# 06_-_TEMP_HUM_CUR_SENSORS.net
KiCad netlist of a schematic drawn in Altium Designer
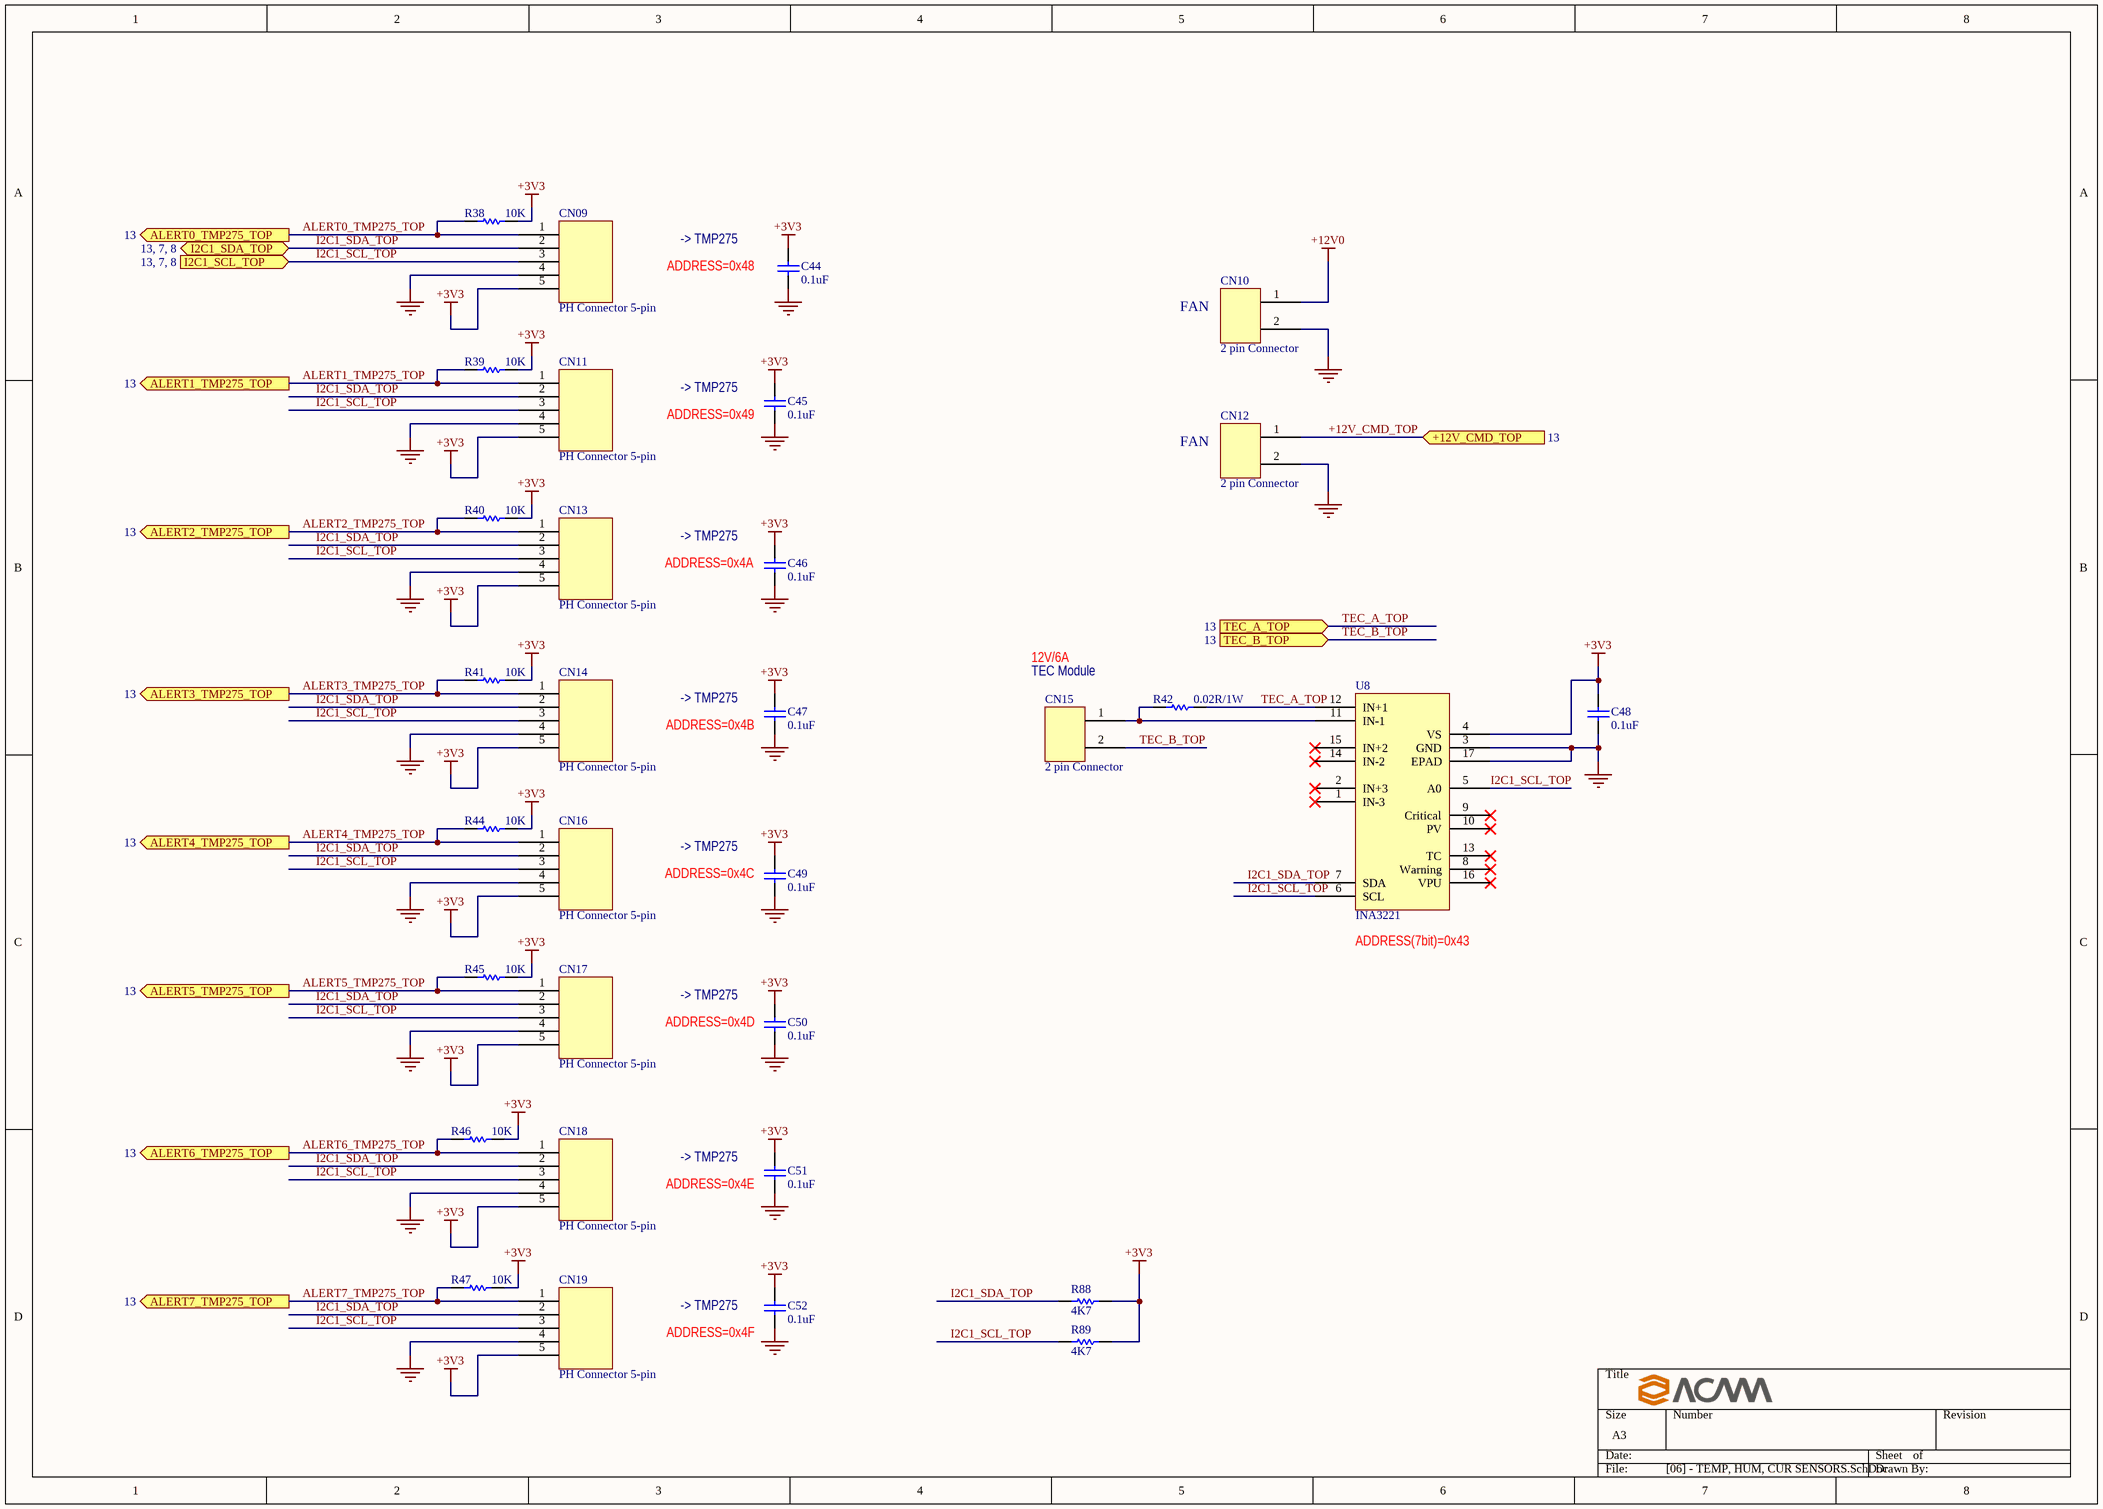
[diagram p0: [06] - TEMP, HUM, CUR SENSORS.SchDoc]

(export (version "E")
  (design (tool "Eeschema 10.0.6"))
  (components
    (comp (ref "C44")
      (value "0.1uF")
      (footprint "0805_C_AUTO")
      (description "Non-Pol SMD Capacitor")
      (libsource (lib "Farzan Custom Library") (part "Cap SMD"))
    )
    (comp (ref "C45")
      (value "0.1uF")
      (footprint "0805_C_AUTO")
      (description "Non-Pol SMD Capacitor")
      (libsource (lib "Farzan Custom Library") (part "Cap SMD"))
    )
    (comp (ref "C46")
      (value "0.1uF")
      (footprint "0805_C_AUTO")
      (description "Non-Pol SMD Capacitor")
      (libsource (lib "Farzan Custom Library") (part "Cap SMD"))
    )
    (comp (ref "C47")
      (value "0.1uF")
      (footprint "0805_C_AUTO")
      (description "Non-Pol SMD Capacitor")
      (libsource (lib "Farzan Custom Library") (part "Cap SMD"))
    )
    (comp (ref "C48")
      (value "0.1uF")
      (footprint "0805_C_AUTO")
      (description "Non-Pol SMD Capacitor")
      (libsource (lib "Farzan Custom Library") (part "Cap SMD"))
    )
    (comp (ref "C49")
      (value "0.1uF")
      (footprint "0805_C_AUTO")
      (description "Non-Pol SMD Capacitor")
      (libsource (lib "Farzan Custom Library") (part "Cap SMD"))
    )
    (comp (ref "C50")
      (value "0.1uF")
      (footprint "0805_C_AUTO")
      (description "Non-Pol SMD Capacitor")
      (libsource (lib "Farzan Custom Library") (part "Cap SMD"))
    )
    (comp (ref "C51")
      (value "0.1uF")
      (footprint "0805_C_AUTO")
      (description "Non-Pol SMD Capacitor")
      (libsource (lib "Farzan Custom Library") (part "Cap SMD"))
    )
    (comp (ref "C52")
      (value "0.1uF")
      (footprint "0805_C_AUTO")
      (description "Non-Pol SMD Capacitor")
      (libsource (lib "Farzan Custom Library") (part "Cap SMD"))
    )
    (comp (ref "CN09")
      (value "PH Connector 5-pin")
      (footprint "PH_5PIN")
      (description "PH Connector , 5 pin, 2mm pitch, straight")
      (libsource (lib "Farzan Custom Library") (part "PH Connector 5-pin"))
    )
    (comp (ref "CN10")
      (value "2 pin Connector")
      (footprint "KF142R_CONN_2PIN")
      (description "KAIFENG Screwless Connector 2 pin")
      (fields (field (name "MANUFACTURER PART NUM") "KF142R"))
      (libsource (lib "Farzan Custom Library") (part "Connector Screwless 2 pin"))
    )
    (comp (ref "CN11")
      (value "PH Connector 5-pin")
      (footprint "PH_5PIN")
      (description "PH Connector , 5 pin, 2mm pitch, straight")
      (libsource (lib "Farzan Custom Library") (part "PH Connector 5-pin"))
    )
    (comp (ref "CN12")
      (value "2 pin Connector")
      (footprint "KF142R_CONN_2PIN")
      (description "KAIFENG Screwless Connector 2 pin")
      (fields (field (name "MANUFACTURER PART NUM") "KF142R"))
      (libsource (lib "Farzan Custom Library") (part "Connector Screwless 2 pin"))
    )
    (comp (ref "CN13")
      (value "PH Connector 5-pin")
      (footprint "PH_5PIN")
      (description "PH Connector , 5 pin, 2mm pitch, straight")
      (libsource (lib "Farzan Custom Library") (part "PH Connector 5-pin"))
    )
    (comp (ref "CN14")
      (value "PH Connector 5-pin")
      (footprint "PH_5PIN")
      (description "PH Connector , 5 pin, 2mm pitch, straight")
      (libsource (lib "Farzan Custom Library") (part "PH Connector 5-pin"))
    )
    (comp (ref "CN15")
      (value "2 pin Connector")
      (footprint "KF142R_CONN_2PIN")
      (description "KAIFENG Screwless Connector 2 pin")
      (fields (field (name "MANUFACTURER PART NUM") "KF142R"))
      (libsource (lib "Farzan Custom Library") (part "Connector Screwless 2 pin"))
    )
    (comp (ref "CN16")
      (value "PH Connector 5-pin")
      (footprint "PH_5PIN")
      (description "PH Connector , 5 pin, 2mm pitch, straight")
      (libsource (lib "Farzan Custom Library") (part "PH Connector 5-pin"))
    )
    (comp (ref "CN17")
      (value "PH Connector 5-pin")
      (footprint "PH_5PIN")
      (description "PH Connector , 5 pin, 2mm pitch, straight")
      (libsource (lib "Farzan Custom Library") (part "PH Connector 5-pin"))
    )
    (comp (ref "CN18")
      (value "PH Connector 5-pin")
      (footprint "PH_5PIN")
      (description "PH Connector , 5 pin, 2mm pitch, straight")
      (libsource (lib "Farzan Custom Library") (part "PH Connector 5-pin"))
    )
    (comp (ref "CN19")
      (value "PH Connector 5-pin")
      (footprint "PH_5PIN")
      (description "PH Connector , 5 pin, 2mm pitch, straight")
      (libsource (lib "Farzan Custom Library") (part "PH Connector 5-pin"))
    )
    (comp (ref "R38")
      (value "10K")
      (footprint "0805_R_AUTO")
      (description "SMD Resistor")
      (fields (field (name "TOLERANCE") "5%"))
      (libsource (lib "Farzan Custom Library") (part "Res SMD"))
    )
    (comp (ref "R39")
      (value "10K")
      (footprint "0805_R_AUTO")
      (description "SMD Resistor")
      (fields (field (name "TOLERANCE") "5%"))
      (libsource (lib "Farzan Custom Library") (part "Res SMD"))
    )
    (comp (ref "R40")
      (value "10K")
      (footprint "0805_R_AUTO")
      (description "SMD Resistor")
      (fields (field (name "TOLERANCE") "5%"))
      (libsource (lib "Farzan Custom Library") (part "Res SMD"))
    )
    (comp (ref "R41")
      (value "10K")
      (footprint "0805_R_AUTO")
      (description "SMD Resistor")
      (fields (field (name "TOLERANCE") "5%"))
      (libsource (lib "Farzan Custom Library") (part "Res SMD"))
    )
    (comp (ref "R42")
      (value "0.02R/1W")
      (footprint "2512_R")
      (description "SMD Resistor")
      (fields (field (name "TOLERANCE") "1%") (field (name "MANUFACTURER PART NUM") "RL2512FK-070R02L"))
      (libsource (lib "Farzan Custom Library") (part "Res SMD"))
    )
    (comp (ref "R44")
      (value "10K")
      (footprint "0805_R_AUTO")
      (description "SMD Resistor")
      (fields (field (name "TOLERANCE") "5%"))
      (libsource (lib "Farzan Custom Library") (part "Res SMD"))
    )
    (comp (ref "R45")
      (value "10K")
      (footprint "0805_R_AUTO")
      (description "SMD Resistor")
      (fields (field (name "TOLERANCE") "5%"))
      (libsource (lib "Farzan Custom Library") (part "Res SMD"))
    )
    (comp (ref "R46")
      (value "10K")
      (footprint "0805_R_AUTO")
      (description "SMD Resistor")
      (fields (field (name "TOLERANCE") "5%"))
      (libsource (lib "Farzan Custom Library") (part "Res SMD"))
    )
    (comp (ref "R47")
      (value "10K")
      (footprint "0805_R_AUTO")
      (description "SMD Resistor")
      (fields (field (name "TOLERANCE") "5%"))
      (libsource (lib "Farzan Custom Library") (part "Res SMD"))
    )
    (comp (ref "R88")
      (value "4K7")
      (footprint "0805_R_AUTO")
      (description "SMD Resistor")
      (fields (field (name "TOLERANCE") "5%"))
      (libsource (lib "Farzan Custom Library") (part "Res SMD"))
    )
    (comp (ref "R89")
      (value "4K7")
      (footprint "0805_R_AUTO")
      (description "SMD Resistor")
      (fields (field (name "TOLERANCE") "5%"))
      (libsource (lib "Farzan Custom Library") (part "Res SMD"))
    )
    (comp (ref "U8")
      (value "INA3221")
      (footprint "QFN-16")
      (fields (field (name "MANUFACTURER PART NUM") "INA3221AIRGVR"))
      (libsource (lib "Farzan Custom Library") (part "INA3221"))
    )
  )
  (nets
    (net (code "1") (name "+3V3") (class "Default")
      (node (ref "C44") (pin "2") (pinfunction "2_2") (pintype "passive"))
      (node (ref "C45") (pin "2") (pinfunction "2_2") (pintype "passive"))
      (node (ref "C46") (pin "2") (pinfunction "2_2") (pintype "passive"))
      (node (ref "C47") (pin "2") (pinfunction "2_2") (pintype "passive"))
      (node (ref "C48") (pin "2") (pinfunction "2_2") (pintype "passive"))
      (node (ref "C49") (pin "2") (pinfunction "2_2") (pintype "passive"))
      (node (ref "C50") (pin "2") (pinfunction "2_2") (pintype "passive"))
      (node (ref "C51") (pin "2") (pinfunction "2_2") (pintype "passive"))
      (node (ref "C52") (pin "2") (pinfunction "2_2") (pintype "passive"))
      (node (ref "CN09") (pin "5") (pinfunction "5_5") (pintype "passive"))
      (node (ref "CN11") (pin "5") (pinfunction "5_5") (pintype "passive"))
      (node (ref "CN13") (pin "5") (pinfunction "5_5") (pintype "passive"))
      (node (ref "CN14") (pin "5") (pinfunction "5_5") (pintype "passive"))
      (node (ref "CN16") (pin "5") (pinfunction "5_5") (pintype "passive"))
      (node (ref "CN17") (pin "5") (pinfunction "5_5") (pintype "passive"))
      (node (ref "CN18") (pin "5") (pinfunction "5_5") (pintype "passive"))
      (node (ref "CN19") (pin "5") (pinfunction "5_5") (pintype "passive"))
      (node (ref "R38") (pin "1") (pinfunction "1_1") (pintype "passive"))
      (node (ref "R39") (pin "1") (pinfunction "1_1") (pintype "passive"))
      (node (ref "R40") (pin "1") (pinfunction "1_1") (pintype "passive"))
      (node (ref "R41") (pin "1") (pinfunction "1_1") (pintype "passive"))
      (node (ref "R44") (pin "1") (pinfunction "1_1") (pintype "passive"))
      (node (ref "R45") (pin "1") (pinfunction "1_1") (pintype "passive"))
      (node (ref "R46") (pin "1") (pinfunction "1_1") (pintype "passive"))
      (node (ref "R47") (pin "1") (pinfunction "1_1") (pintype "passive"))
      (node (ref "R88") (pin "2") (pinfunction "2_2") (pintype "passive"))
      (node (ref "R89") (pin "2") (pinfunction "2_2") (pintype "passive"))
      (node (ref "U8") (pin "4") (pinfunction "VS_4") (pintype "power_in"))
    )
    (net (code "2") (name "+12V0") (class "Default")
      (node (ref "CN10") (pin "1") (pinfunction "1_1") (pintype "passive"))
    )
    (net (code "3") (name "/+12V_CMD_TOP") (class "Default")
      (node (ref "CN12") (pin "1") (pinfunction "1_1") (pintype "passive"))
    )
    (net (code "4") (name "/ALERT0_TMP275_TOP") (class "Default")
      (node (ref "CN09") (pin "1") (pinfunction "1_1") (pintype "passive"))
      (node (ref "R38") (pin "2") (pinfunction "2_2") (pintype "passive"))
    )
    (net (code "5") (name "/ALERT1_TMP275_TOP") (class "Default")
      (node (ref "CN11") (pin "1") (pinfunction "1_1") (pintype "passive"))
      (node (ref "R39") (pin "2") (pinfunction "2_2") (pintype "passive"))
    )
    (net (code "6") (name "/ALERT2_TMP275_TOP") (class "Default")
      (node (ref "CN13") (pin "1") (pinfunction "1_1") (pintype "passive"))
      (node (ref "R40") (pin "2") (pinfunction "2_2") (pintype "passive"))
    )
    (net (code "7") (name "/ALERT3_TMP275_TOP") (class "Default")
      (node (ref "CN14") (pin "1") (pinfunction "1_1") (pintype "passive"))
      (node (ref "R41") (pin "2") (pinfunction "2_2") (pintype "passive"))
    )
    (net (code "8") (name "/ALERT4_TMP275_TOP") (class "Default")
      (node (ref "CN16") (pin "1") (pinfunction "1_1") (pintype "passive"))
      (node (ref "R44") (pin "2") (pinfunction "2_2") (pintype "passive"))
    )
    (net (code "9") (name "/ALERT5_TMP275_TOP") (class "Default")
      (node (ref "CN17") (pin "1") (pinfunction "1_1") (pintype "passive"))
      (node (ref "R45") (pin "2") (pinfunction "2_2") (pintype "passive"))
    )
    (net (code "10") (name "/ALERT6_TMP275_TOP") (class "Default")
      (node (ref "CN18") (pin "1") (pinfunction "1_1") (pintype "passive"))
      (node (ref "R46") (pin "2") (pinfunction "2_2") (pintype "passive"))
    )
    (net (code "11") (name "/ALERT7_TMP275_TOP") (class "Default")
      (node (ref "CN19") (pin "1") (pinfunction "1_1") (pintype "passive"))
      (node (ref "R47") (pin "2") (pinfunction "2_2") (pintype "passive"))
    )
    (net (code "12") (name "/I2C1_SCL_TOP") (class "Default")
      (node (ref "CN09") (pin "3") (pinfunction "3_3") (pintype "passive"))
      (node (ref "CN11") (pin "3") (pinfunction "3_3") (pintype "passive"))
      (node (ref "CN13") (pin "3") (pinfunction "3_3") (pintype "passive"))
      (node (ref "CN14") (pin "3") (pinfunction "3_3") (pintype "passive"))
      (node (ref "CN16") (pin "3") (pinfunction "3_3") (pintype "passive"))
      (node (ref "CN17") (pin "3") (pinfunction "3_3") (pintype "passive"))
      (node (ref "CN18") (pin "3") (pinfunction "3_3") (pintype "passive"))
      (node (ref "CN19") (pin "3") (pinfunction "3_3") (pintype "passive"))
      (node (ref "R89") (pin "1") (pinfunction "1_1") (pintype "passive"))
      (node (ref "U8") (pin "5") (pinfunction "A0_5") (pintype "passive"))
      (node (ref "U8") (pin "6") (pinfunction "SCL_6") (pintype "passive"))
    )
    (net (code "13") (name "/I2C1_SDA_TOP") (class "Default")
      (node (ref "CN09") (pin "2") (pinfunction "2_2") (pintype "passive"))
      (node (ref "CN11") (pin "2") (pinfunction "2_2") (pintype "passive"))
      (node (ref "CN13") (pin "2") (pinfunction "2_2") (pintype "passive"))
      (node (ref "CN14") (pin "2") (pinfunction "2_2") (pintype "passive"))
      (node (ref "CN16") (pin "2") (pinfunction "2_2") (pintype "passive"))
      (node (ref "CN17") (pin "2") (pinfunction "2_2") (pintype "passive"))
      (node (ref "CN18") (pin "2") (pinfunction "2_2") (pintype "passive"))
      (node (ref "CN19") (pin "2") (pinfunction "2_2") (pintype "passive"))
      (node (ref "R88") (pin "1") (pinfunction "1_1") (pintype "passive"))
      (node (ref "U8") (pin "7") (pinfunction "SDA_7") (pintype "passive"))
    )
    (net (code "14") (name "/TEC_A_TOP") (class "Default")
      (node (ref "R42") (pin "2") (pinfunction "2_2") (pintype "passive"))
      (node (ref "U8") (pin "12") (pinfunction "IN+1_12") (pintype "passive"))
    )
    (net (code "15") (name "/TEC_B_TOP") (class "Default")
      (node (ref "CN15") (pin "2") (pinfunction "2_2") (pintype "passive"))
    )
    (net (code "16") (name "GND") (class "Default")
      (node (ref "C44") (pin "1") (pinfunction "1_1") (pintype "passive"))
      (node (ref "C45") (pin "1") (pinfunction "1_1") (pintype "passive"))
      (node (ref "C46") (pin "1") (pinfunction "1_1") (pintype "passive"))
      (node (ref "C47") (pin "1") (pinfunction "1_1") (pintype "passive"))
      (node (ref "C48") (pin "1") (pinfunction "1_1") (pintype "passive"))
      (node (ref "C49") (pin "1") (pinfunction "1_1") (pintype "passive"))
      (node (ref "C50") (pin "1") (pinfunction "1_1") (pintype "passive"))
      (node (ref "C51") (pin "1") (pinfunction "1_1") (pintype "passive"))
      (node (ref "C52") (pin "1") (pinfunction "1_1") (pintype "passive"))
      (node (ref "CN09") (pin "4") (pinfunction "4_4") (pintype "passive"))
      (node (ref "CN10") (pin "2") (pinfunction "2_2") (pintype "passive"))
      (node (ref "CN11") (pin "4") (pinfunction "4_4") (pintype "passive"))
      (node (ref "CN12") (pin "2") (pinfunction "2_2") (pintype "passive"))
      (node (ref "CN13") (pin "4") (pinfunction "4_4") (pintype "passive"))
      (node (ref "CN14") (pin "4") (pinfunction "4_4") (pintype "passive"))
      (node (ref "CN16") (pin "4") (pinfunction "4_4") (pintype "passive"))
      (node (ref "CN17") (pin "4") (pinfunction "4_4") (pintype "passive"))
      (node (ref "CN18") (pin "4") (pinfunction "4_4") (pintype "passive"))
      (node (ref "CN19") (pin "4") (pinfunction "4_4") (pintype "passive"))
      (node (ref "U8") (pin "17") (pinfunction "EPAD_17") (pintype "passive"))
      (node (ref "U8") (pin "3") (pinfunction "GND_3") (pintype "power_in"))
    )
    (net (code "17") (name "Net-(U8-IN-1)") (class "Default")
      (node (ref "CN15") (pin "1") (pinfunction "1_1") (pintype "passive"))
      (node (ref "R42") (pin "1") (pinfunction "1_1") (pintype "passive"))
      (node (ref "U8") (pin "11") (pinfunction "IN-1_11") (pintype "passive"))
    )
    (net (code "18") (name "unconnected-(U8-Critical-Pad9)") (class "Default")
      (node (ref "U8") (pin "9") (pinfunction "Critical_9") (pintype "passive+no_connect"))
    )
    (net (code "19") (name "unconnected-(U8-IN+2-Pad15)") (class "Default")
      (node (ref "U8") (pin "15") (pinfunction "IN+2_15") (pintype "passive+no_connect"))
    )
    (net (code "20") (name "unconnected-(U8-IN+3-Pad2)") (class "Default")
      (node (ref "U8") (pin "2") (pinfunction "IN+3_2") (pintype "passive+no_connect"))
    )
    (net (code "21") (name "unconnected-(U8-IN-2-Pad14)") (class "Default")
      (node (ref "U8") (pin "14") (pinfunction "IN-2_14") (pintype "passive+no_connect"))
    )
    (net (code "22") (name "unconnected-(U8-IN-3-Pad1)") (class "Default")
      (node (ref "U8") (pin "1") (pinfunction "IN-3_1") (pintype "passive+no_connect"))
    )
    (net (code "23") (name "unconnected-(U8-PV-Pad10)") (class "Default")
      (node (ref "U8") (pin "10") (pinfunction "PV_10") (pintype "passive+no_connect"))
    )
    (net (code "24") (name "unconnected-(U8-TC-Pad13)") (class "Default")
      (node (ref "U8") (pin "13") (pinfunction "TC_13") (pintype "passive+no_connect"))
    )
    (net (code "25") (name "unconnected-(U8-VPU-Pad16)") (class "Default")
      (node (ref "U8") (pin "16") (pinfunction "VPU_16") (pintype "passive+no_connect"))
    )
    (net (code "26") (name "unconnected-(U8-Warning-Pad8)") (class "Default")
      (node (ref "U8") (pin "8") (pinfunction "Warning_8") (pintype "passive+no_connect"))
    )
  )
)
